# NB-IoT_Module.net
KiCad netlist of a schematic drawn in Altium Designer
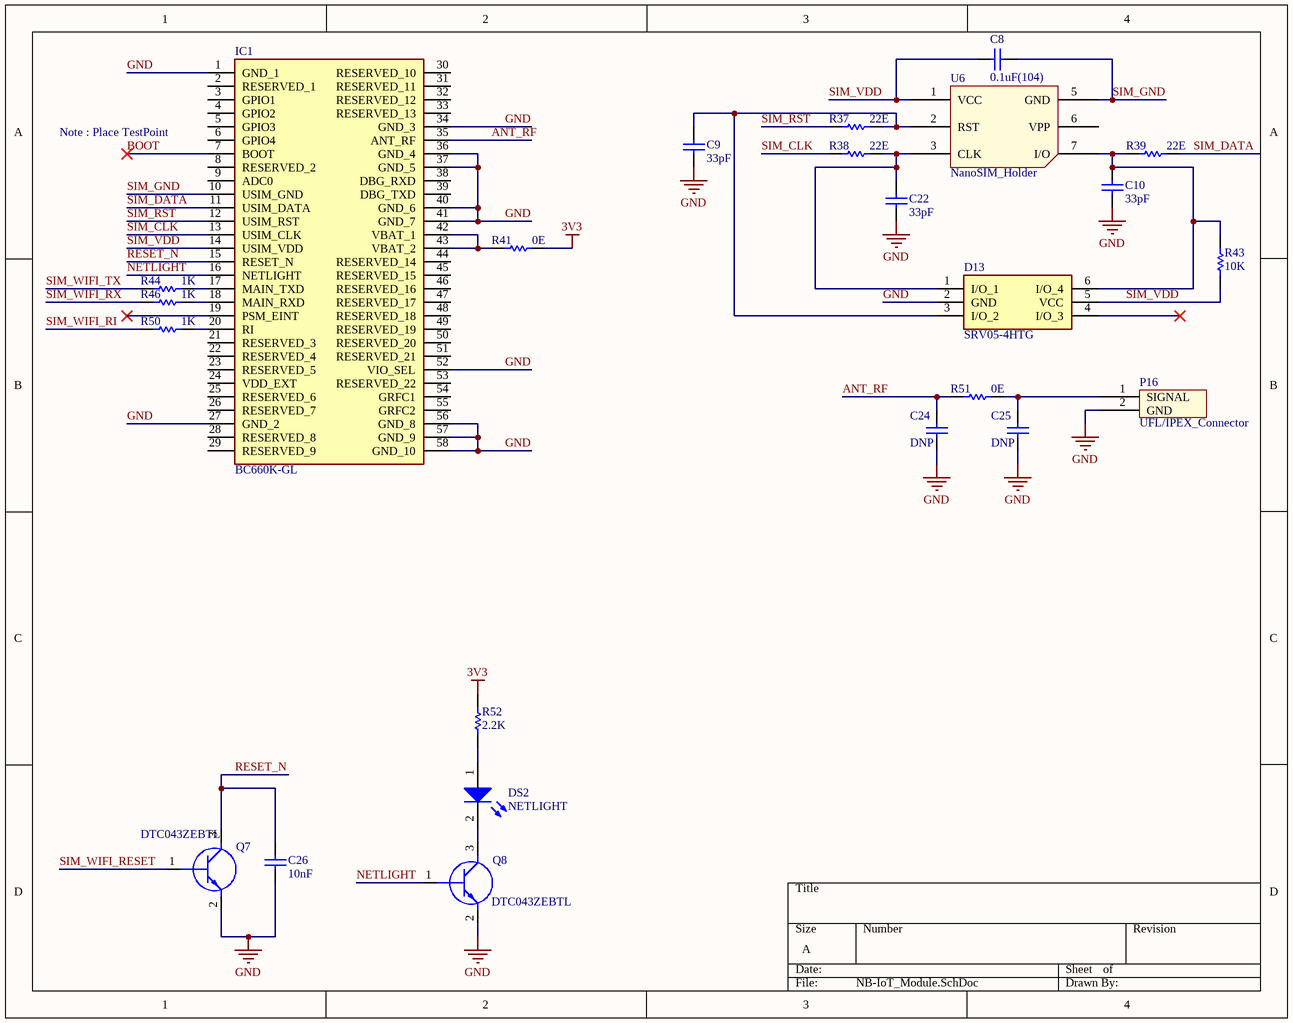
[diagram p0: NB-IoT_Module.SchDoc]

(export (version "E")
  (design (tool "Eeschema 10.0.6"))
  (components
    (comp (ref "C8")
      (value "0.1uF(104)")
      (footprint "0805")
      (description "Capacitor")
      (fields (field (name "Comment") "Cap") (field (name "PUBLISHER") "Altium Limited"))
      (libsource (lib "Miscellaneous Devices") (part "Cap"))
    )
    (comp (ref "C9")
      (value "33pF")
      (footprint "0805")
      (description "Capacitor")
      (fields (field (name "Comment") "Cap") (field (name "PUBLISHER") "Altium Limited"))
      (libsource (lib "Miscellaneous Devices") (part "Cap"))
    )
    (comp (ref "C10")
      (value "33pF")
      (footprint "0805")
      (description "Capacitor")
      (fields (field (name "Comment") "Cap") (field (name "PUBLISHER") "Altium Limited"))
      (libsource (lib "Miscellaneous Devices") (part "Cap"))
    )
    (comp (ref "C22")
      (value "33pF")
      (footprint "0805")
      (description "Capacitor")
      (fields (field (name "Comment") "Cap") (field (name "PUBLISHER") "Altium Limited"))
      (libsource (lib "Miscellaneous Devices") (part "Cap"))
    )
    (comp (ref "C24")
      (value "DNP")
      (footprint "0805")
      (description "Capacitor")
      (fields (field (name "Comment") "Cap") (field (name "PUBLISHER") "Altium Limited"))
      (libsource (lib "Miscellaneous Devices") (part "Cap"))
    )
    (comp (ref "C25")
      (value "DNP")
      (footprint "0805")
      (description "Capacitor")
      (fields (field (name "Comment") "Cap") (field (name "PUBLISHER") "Altium Limited"))
      (libsource (lib "Miscellaneous Devices") (part "Cap"))
    )
    (comp (ref "C26")
      (value "10nF")
      (footprint "0805")
      (description "Capacitor")
      (fields (field (name "Comment") "Cap") (field (name "PUBLISHER") "Altium Limited"))
      (libsource (lib "Miscellaneous Devices") (part "Cap"))
    )
    (comp (ref "D13")
      (value "SRV05-4HTG")
      (footprint "SamacSys:SOT95P280X145-6N")
      (description "TVS Diode (Uni-directional)")
      (fields (field (name "MOUSER PART NUMBER") "576-SRV05-4HTG"))
      (libsource (lib "SamacSys") (part "SRV05-4HTG"))
    )
    (comp (ref "DS2")
      (value "NETLIGHT")
      (footprint "0805_LED")
      (description "LED 5mm Diameter")
      (fields (field (name "PUBLISHER") "Altium Limited"))
      (libsource (lib "Miscellaneous Devices") (part "LED0"))
    )
    (comp (ref "IC1")
      (value "BC660K-GL")
      (footprint "SamacSys:BC660KGL")
      (description "Integrated Circuit")
      (libsource (lib "*") (part "BC660K-GL"))
    )
    (comp (ref "P16")
      (value "UFL/IPEX_Connector")
      (footprint "RFAnt_Connector")
      (libsource (lib "SchLib") (part "UFL_Connector"))
    )
    (comp (ref "Q7")
      (value "DTC043ZEBTL")
      (footprint "SOTFL50P160X85-3N")
      (description "Transistor BJT NPN")
      (fields (field (name "MOUSER PART NUMBER") "755-DTC043ZEBTL"))
      (libsource (lib "*") (part "DTC043ZEBTL"))
    )
    (comp (ref "Q8")
      (value "DTC043ZEBTL")
      (footprint "SOTFL50P160X85-3N")
      (description "Transistor BJT NPN")
      (fields (field (name "MOUSER PART NUMBER") "755-DTC043ZEBTL"))
      (libsource (lib "*") (part "DTC043ZEBTL"))
    )
    (comp (ref "R37")
      (value "22E")
      (footprint "SMDlibrary:0805")
      (description "Resistor")
      (fields (field (name "Comment") "Res1") (field (name "PUBLISHER") "Altium Limited"))
      (libsource (lib "Miscellaneous Devices") (part "Res1"))
    )
    (comp (ref "R38")
      (value "22E")
      (footprint "SMDlibrary:0805")
      (description "Resistor")
      (fields (field (name "Comment") "Res1") (field (name "PUBLISHER") "Altium Limited"))
      (libsource (lib "Miscellaneous Devices") (part "Res1"))
    )
    (comp (ref "R39")
      (value "22E")
      (footprint "SMDlibrary:0805")
      (description "Resistor")
      (fields (field (name "Comment") "Res1") (field (name "PUBLISHER") "Altium Limited"))
      (libsource (lib "Miscellaneous Devices") (part "Res1"))
    )
    (comp (ref "R41")
      (value "0E")
      (footprint "SMDlibrary:0805")
      (description "Resistor")
      (fields (field (name "Comment") "Res1") (field (name "PUBLISHER") "Altium Limited"))
      (libsource (lib "Miscellaneous Devices") (part "Res1"))
    )
    (comp (ref "R43")
      (value "10K")
      (footprint "SMDlibrary:0805")
      (description "Resistor")
      (fields (field (name "Comment") "Res1") (field (name "PUBLISHER") "Altium Limited"))
      (libsource (lib "Miscellaneous Devices") (part "Res1"))
    )
    (comp (ref "R44")
      (value "1K")
      (footprint "SMDlibrary:0805")
      (description "Resistor")
      (fields (field (name "Comment") "Res1") (field (name "PUBLISHER") "Altium Limited"))
      (libsource (lib "Miscellaneous Devices") (part "Res1"))
    )
    (comp (ref "R46")
      (value "1K")
      (footprint "SMDlibrary:0805")
      (description "Resistor")
      (fields (field (name "Comment") "Res1") (field (name "PUBLISHER") "Altium Limited"))
      (libsource (lib "Miscellaneous Devices") (part "Res1"))
    )
    (comp (ref "R50")
      (value "1K")
      (footprint "SMDlibrary:0805")
      (description "Resistor")
      (fields (field (name "Comment") "Res1") (field (name "PUBLISHER") "Altium Limited"))
      (libsource (lib "Miscellaneous Devices") (part "Res1"))
    )
    (comp (ref "R51")
      (value "0E")
      (footprint "0805")
      (description "Resistor")
      (fields (field (name "Comment") "Res1") (field (name "PUBLISHER") "Altium Limited"))
      (libsource (lib "Miscellaneous Devices") (part "Res1"))
    )
    (comp (ref "R52")
      (value "2.2K")
      (footprint "SMDlibrary:0805")
      (description "Resistor")
      (fields (field (name "Comment") "Res1") (field (name "PUBLISHER") "Altium Limited"))
      (libsource (lib "Miscellaneous Devices") (part "Res1"))
    )
    (comp (ref "U6")
      (value "NanoSIM_Holder")
      (footprint "Nano_SIMCard_Holder")
      (libsource (lib "SchLib") (part "NanoSIM_Holder"))
    )
  )
  (nets
    (net (code "1") (name "/ANT_RF") (class "Default")
      (node (ref "C24") (pin "1") (pinfunction "1_1") (pintype "passive"))
      (node (ref "IC1") (pin "35") (pinfunction "ANT_RF_35") (pintype "passive"))
      (node (ref "R51") (pin "2") (pinfunction "2_2") (pintype "passive"))
    )
    (net (code "2") (name "/BOOT") (class "Default")
      (node (ref "IC1") (pin "7") (pinfunction "BOOT_7") (pintype "passive+no_connect"))
    )
    (net (code "3") (name "/NETLIGHT") (class "Default")
      (node (ref "IC1") (pin "16") (pinfunction "NETLIGHT_16") (pintype "passive"))
      (node (ref "Q8") (pin "1") (pinfunction "B_1") (pintype "passive"))
    )
    (net (code "4") (name "/RESET_N") (class "Default")
      (node (ref "C26") (pin "1") (pinfunction "1_1") (pintype "passive"))
      (node (ref "IC1") (pin "15") (pinfunction "RESET_N_15") (pintype "passive"))
      (node (ref "Q7") (pin "3") (pinfunction "C_3") (pintype "passive"))
    )
    (net (code "5") (name "/SIM_CLK") (class "Default")
      (node (ref "IC1") (pin "13") (pinfunction "USIM_CLK_13") (pintype "passive"))
      (node (ref "R38") (pin "2") (pinfunction "2_2") (pintype "passive"))
    )
    (net (code "6") (name "/SIM_DATA") (class "Default")
      (node (ref "IC1") (pin "11") (pinfunction "USIM_DATA_11") (pintype "passive"))
      (node (ref "R39") (pin "1") (pinfunction "1_1") (pintype "passive"))
    )
    (net (code "7") (name "/SIM_GND") (class "Default")
      (node (ref "C8") (pin "1") (pinfunction "1_1") (pintype "passive"))
      (node (ref "IC1") (pin "10") (pinfunction "USIM_GND_10") (pintype "passive"))
      (node (ref "U6") (pin "5") (pinfunction "GND_5") (pintype "passive"))
    )
    (net (code "8") (name "/SIM_RST") (class "Default")
      (node (ref "IC1") (pin "12") (pinfunction "USIM_RST_12") (pintype "passive"))
      (node (ref "R37") (pin "2") (pinfunction "2_2") (pintype "passive"))
    )
    (net (code "9") (name "/SIM_VDD") (class "Default")
      (node (ref "C8") (pin "2") (pinfunction "2_2") (pintype "passive"))
      (node (ref "D13") (pin "5") (pinfunction "VCC_5") (pintype "passive"))
      (node (ref "IC1") (pin "14") (pinfunction "USIM_VDD_14") (pintype "passive"))
      (node (ref "R43") (pin "2") (pinfunction "2_2") (pintype "passive"))
      (node (ref "U6") (pin "1") (pinfunction "VCC_1") (pintype "passive"))
    )
    (net (code "10") (name "/SIM_WIFI_RESET") (class "Default")
      (node (ref "Q7") (pin "1") (pinfunction "B_1") (pintype "passive"))
    )
    (net (code "11") (name "/SIM_WIFI_RI") (class "Default")
      (node (ref "R50") (pin "2") (pinfunction "2_2") (pintype "passive"))
    )
    (net (code "12") (name "/SIM_WIFI_RX") (class "Default")
      (node (ref "R46") (pin "2") (pinfunction "2_2") (pintype "passive"))
    )
    (net (code "13") (name "/SIM_WIFI_TX") (class "Default")
      (node (ref "R44") (pin "2") (pinfunction "2_2") (pintype "passive"))
    )
    (net (code "14") (name "3V3") (class "Default")
      (node (ref "R41") (pin "1") (pinfunction "1_1") (pintype "passive"))
      (node (ref "R52") (pin "2") (pinfunction "2_2") (pintype "passive"))
    )
    (net (code "15") (name "GND") (class "Default")
      (node (ref "C10") (pin "1") (pinfunction "1_1") (pintype "passive"))
      (node (ref "C22") (pin "1") (pinfunction "1_1") (pintype "passive"))
      (node (ref "C24") (pin "2") (pinfunction "2_2") (pintype "passive"))
      (node (ref "C25") (pin "2") (pinfunction "2_2") (pintype "passive"))
      (node (ref "C26") (pin "2") (pinfunction "2_2") (pintype "passive"))
      (node (ref "C9") (pin "1") (pinfunction "1_1") (pintype "passive"))
      (node (ref "D13") (pin "2") (pinfunction "GND_2") (pintype "passive"))
      (node (ref "IC1") (pin "1") (pinfunction "GND_1_1") (pintype "passive"))
      (node (ref "IC1") (pin "27") (pinfunction "GND_2_27") (pintype "passive"))
      (node (ref "IC1") (pin "34") (pinfunction "GND_3_34") (pintype "passive"))
      (node (ref "IC1") (pin "36") (pinfunction "GND_4_36") (pintype "passive"))
      (node (ref "IC1") (pin "37") (pinfunction "GND_5_37") (pintype "passive"))
      (node (ref "IC1") (pin "40") (pinfunction "GND_6_40") (pintype "passive"))
      (node (ref "IC1") (pin "41") (pinfunction "GND_7_41") (pintype "passive"))
      (node (ref "IC1") (pin "52") (pinfunction "VIO_SEL_52") (pintype "passive"))
      (node (ref "IC1") (pin "56") (pinfunction "GND_8_56") (pintype "passive"))
      (node (ref "IC1") (pin "57") (pinfunction "GND_9_57") (pintype "passive"))
      (node (ref "IC1") (pin "58") (pinfunction "GND_10_58") (pintype "passive"))
      (node (ref "P16") (pin "2") (pinfunction "GND_2") (pintype "passive"))
      (node (ref "Q7") (pin "2") (pinfunction "E_2") (pintype "passive"))
      (node (ref "Q8") (pin "2") (pinfunction "E_2") (pintype "passive"))
    )
    (net (code "16") (name "Net-(D13-I{slash}O_1)") (class "Default")
      (node (ref "C22") (pin "2") (pinfunction "2_2") (pintype "passive"))
      (node (ref "D13") (pin "1") (pinfunction "I/O_1_1") (pintype "passive"))
      (node (ref "R38") (pin "1") (pinfunction "1_1") (pintype "passive"))
      (node (ref "U6") (pin "3") (pinfunction "CLK_3") (pintype "passive"))
    )
    (net (code "17") (name "Net-(D13-I{slash}O_2)") (class "Default")
      (node (ref "C9") (pin "2") (pinfunction "2_2") (pintype "passive"))
      (node (ref "D13") (pin "3") (pinfunction "I/O_2_3") (pintype "passive"))
      (node (ref "R37") (pin "1") (pinfunction "1_1") (pintype "passive"))
      (node (ref "U6") (pin "2") (pinfunction "RST_2") (pintype "passive"))
    )
    (net (code "18") (name "Net-(D13-I{slash}O_4)") (class "Default")
      (node (ref "C10") (pin "2") (pinfunction "2_2") (pintype "passive"))
      (node (ref "D13") (pin "6") (pinfunction "I/O_4_6") (pintype "passive"))
      (node (ref "R39") (pin "2") (pinfunction "2_2") (pintype "passive"))
      (node (ref "R43") (pin "1") (pinfunction "1_1") (pintype "passive"))
      (node (ref "U6") (pin "7") (pinfunction "I/O_7") (pintype "passive"))
    )
    (net (code "19") (name "Net-(DS2-A)") (class "Default")
      (node (ref "DS2") (pin "1") (pinfunction "A_1") (pintype "passive"))
      (node (ref "R52") (pin "1") (pinfunction "1_1") (pintype "passive"))
    )
    (net (code "20") (name "Net-(DS2-K)") (class "Default")
      (node (ref "DS2") (pin "2") (pinfunction "K_2") (pintype "passive"))
      (node (ref "Q8") (pin "3") (pinfunction "C_3") (pintype "passive"))
    )
    (net (code "21") (name "Net-(IC1-MAIN_RXD)") (class "Default")
      (node (ref "IC1") (pin "18") (pinfunction "MAIN_RXD_18") (pintype "passive"))
      (node (ref "R46") (pin "1") (pinfunction "1_1") (pintype "passive"))
    )
    (net (code "22") (name "Net-(IC1-MAIN_TXD)") (class "Default")
      (node (ref "IC1") (pin "17") (pinfunction "MAIN_TXD_17") (pintype "passive"))
      (node (ref "R44") (pin "1") (pinfunction "1_1") (pintype "passive"))
    )
    (net (code "23") (name "Net-(IC1-RI)") (class "Default")
      (node (ref "IC1") (pin "20") (pinfunction "RI_20") (pintype "passive"))
      (node (ref "R50") (pin "1") (pinfunction "1_1") (pintype "passive"))
    )
    (net (code "24") (name "Net-(IC1-VBAT_1)") (class "Default")
      (node (ref "IC1") (pin "42") (pinfunction "VBAT_1_42") (pintype "passive"))
      (node (ref "IC1") (pin "43") (pinfunction "VBAT_2_43") (pintype "passive"))
      (node (ref "R41") (pin "2") (pinfunction "2_2") (pintype "passive"))
    )
    (net (code "25") (name "Net-(P16-SIGNAL)") (class "Default")
      (node (ref "C25") (pin "1") (pinfunction "1_1") (pintype "passive"))
      (node (ref "P16") (pin "1") (pinfunction "SIGNAL_1") (pintype "passive"))
      (node (ref "R51") (pin "1") (pinfunction "1_1") (pintype "passive"))
    )
    (net (code "26") (name "unconnected-(D13-I{slash}O_3-Pad4)") (class "Default")
      (node (ref "D13") (pin "4") (pinfunction "I/O_3_4") (pintype "passive+no_connect"))
    )
    (net (code "27") (name "unconnected-(IC1-ADC0-Pad9)") (class "Default")
      (node (ref "IC1") (pin "9") (pinfunction "ADC0_9") (pintype "passive"))
    )
    (net (code "28") (name "unconnected-(IC1-DBG_RXD-Pad38)") (class "Default")
      (node (ref "IC1") (pin "38") (pinfunction "DBG_RXD_38") (pintype "passive"))
    )
    (net (code "29") (name "unconnected-(IC1-DBG_TXD-Pad39)") (class "Default")
      (node (ref "IC1") (pin "39") (pinfunction "DBG_TXD_39") (pintype "passive"))
    )
    (net (code "30") (name "unconnected-(IC1-GPIO1-Pad3)") (class "Default")
      (node (ref "IC1") (pin "3") (pinfunction "GPIO1_3") (pintype "passive"))
    )
    (net (code "31") (name "unconnected-(IC1-GPIO2-Pad4)") (class "Default")
      (node (ref "IC1") (pin "4") (pinfunction "GPIO2_4") (pintype "passive"))
    )
    (net (code "32") (name "unconnected-(IC1-GPIO3-Pad5)") (class "Default")
      (node (ref "IC1") (pin "5") (pinfunction "GPIO3_5") (pintype "passive"))
    )
    (net (code "33") (name "unconnected-(IC1-GPIO4-Pad6)") (class "Default")
      (node (ref "IC1") (pin "6") (pinfunction "GPIO4_6") (pintype "passive"))
    )
    (net (code "34") (name "unconnected-(IC1-GRFC1-Pad54)") (class "Default")
      (node (ref "IC1") (pin "54") (pinfunction "GRFC1_54") (pintype "passive"))
    )
    (net (code "35") (name "unconnected-(IC1-GRFC2-Pad55)") (class "Default")
      (node (ref "IC1") (pin "55") (pinfunction "GRFC2_55") (pintype "passive"))
    )
    (net (code "36") (name "unconnected-(IC1-PSM_EINT-Pad19)") (class "Default")
      (node (ref "IC1") (pin "19") (pinfunction "PSM_EINT_19") (pintype "passive+no_connect"))
    )
    (net (code "37") (name "unconnected-(IC1-RESERVED_1-Pad2)") (class "Default")
      (node (ref "IC1") (pin "2") (pinfunction "RESERVED_1_2") (pintype "passive"))
    )
    (net (code "38") (name "unconnected-(IC1-RESERVED_2-Pad8)") (class "Default")
      (node (ref "IC1") (pin "8") (pinfunction "RESERVED_2_8") (pintype "passive"))
    )
    (net (code "39") (name "unconnected-(IC1-RESERVED_3-Pad21)") (class "Default")
      (node (ref "IC1") (pin "21") (pinfunction "RESERVED_3_21") (pintype "passive"))
    )
    (net (code "40") (name "unconnected-(IC1-RESERVED_4-Pad22)") (class "Default")
      (node (ref "IC1") (pin "22") (pinfunction "RESERVED_4_22") (pintype "passive"))
    )
    (net (code "41") (name "unconnected-(IC1-RESERVED_5-Pad23)") (class "Default")
      (node (ref "IC1") (pin "23") (pinfunction "RESERVED_5_23") (pintype "passive"))
    )
    (net (code "42") (name "unconnected-(IC1-RESERVED_6-Pad25)") (class "Default")
      (node (ref "IC1") (pin "25") (pinfunction "RESERVED_6_25") (pintype "passive"))
    )
    (net (code "43") (name "unconnected-(IC1-RESERVED_7-Pad26)") (class "Default")
      (node (ref "IC1") (pin "26") (pinfunction "RESERVED_7_26") (pintype "passive"))
    )
    (net (code "44") (name "unconnected-(IC1-RESERVED_8-Pad28)") (class "Default")
      (node (ref "IC1") (pin "28") (pinfunction "RESERVED_8_28") (pintype "passive"))
    )
    (net (code "45") (name "unconnected-(IC1-RESERVED_9-Pad29)") (class "Default")
      (node (ref "IC1") (pin "29") (pinfunction "RESERVED_9_29") (pintype "passive"))
    )
    (net (code "46") (name "unconnected-(IC1-RESERVED_10-Pad30)") (class "Default")
      (node (ref "IC1") (pin "30") (pinfunction "RESERVED_10_30") (pintype "passive"))
    )
    (net (code "47") (name "unconnected-(IC1-RESERVED_11-Pad31)") (class "Default")
      (node (ref "IC1") (pin "31") (pinfunction "RESERVED_11_31") (pintype "passive"))
    )
    (net (code "48") (name "unconnected-(IC1-RESERVED_12-Pad32)") (class "Default")
      (node (ref "IC1") (pin "32") (pinfunction "RESERVED_12_32") (pintype "passive"))
    )
    (net (code "49") (name "unconnected-(IC1-RESERVED_13-Pad33)") (class "Default")
      (node (ref "IC1") (pin "33") (pinfunction "RESERVED_13_33") (pintype "passive"))
    )
    (net (code "50") (name "unconnected-(IC1-RESERVED_14-Pad44)") (class "Default")
      (node (ref "IC1") (pin "44") (pinfunction "RESERVED_14_44") (pintype "passive"))
    )
    (net (code "51") (name "unconnected-(IC1-RESERVED_15-Pad45)") (class "Default")
      (node (ref "IC1") (pin "45") (pinfunction "RESERVED_15_45") (pintype "passive"))
    )
    (net (code "52") (name "unconnected-(IC1-RESERVED_16-Pad46)") (class "Default")
      (node (ref "IC1") (pin "46") (pinfunction "RESERVED_16_46") (pintype "passive"))
    )
    (net (code "53") (name "unconnected-(IC1-RESERVED_17-Pad47)") (class "Default")
      (node (ref "IC1") (pin "47") (pinfunction "RESERVED_17_47") (pintype "passive"))
    )
    (net (code "54") (name "unconnected-(IC1-RESERVED_18-Pad48)") (class "Default")
      (node (ref "IC1") (pin "48") (pinfunction "RESERVED_18_48") (pintype "passive"))
    )
    (net (code "55") (name "unconnected-(IC1-RESERVED_19-Pad49)") (class "Default")
      (node (ref "IC1") (pin "49") (pinfunction "RESERVED_19_49") (pintype "passive"))
    )
    (net (code "56") (name "unconnected-(IC1-RESERVED_20-Pad50)") (class "Default")
      (node (ref "IC1") (pin "50") (pinfunction "RESERVED_20_50") (pintype "passive"))
    )
    (net (code "57") (name "unconnected-(IC1-RESERVED_21-Pad51)") (class "Default")
      (node (ref "IC1") (pin "51") (pinfunction "RESERVED_21_51") (pintype "passive"))
    )
    (net (code "58") (name "unconnected-(IC1-RESERVED_22-Pad53)") (class "Default")
      (node (ref "IC1") (pin "53") (pinfunction "RESERVED_22_53") (pintype "passive"))
    )
    (net (code "59") (name "unconnected-(IC1-VDD_EXT-Pad24)") (class "Default")
      (node (ref "IC1") (pin "24") (pinfunction "VDD_EXT_24") (pintype "passive"))
    )
    (net (code "60") (name "unconnected-(U6-VPP-Pad6)") (class "Default")
      (node (ref "U6") (pin "6") (pinfunction "VPP_6") (pintype "passive"))
    )
  )
)
